# Adafruit_tftcaptouchshield_rev_C.net
KiCad netlist of a schematic drawn in EAGLE
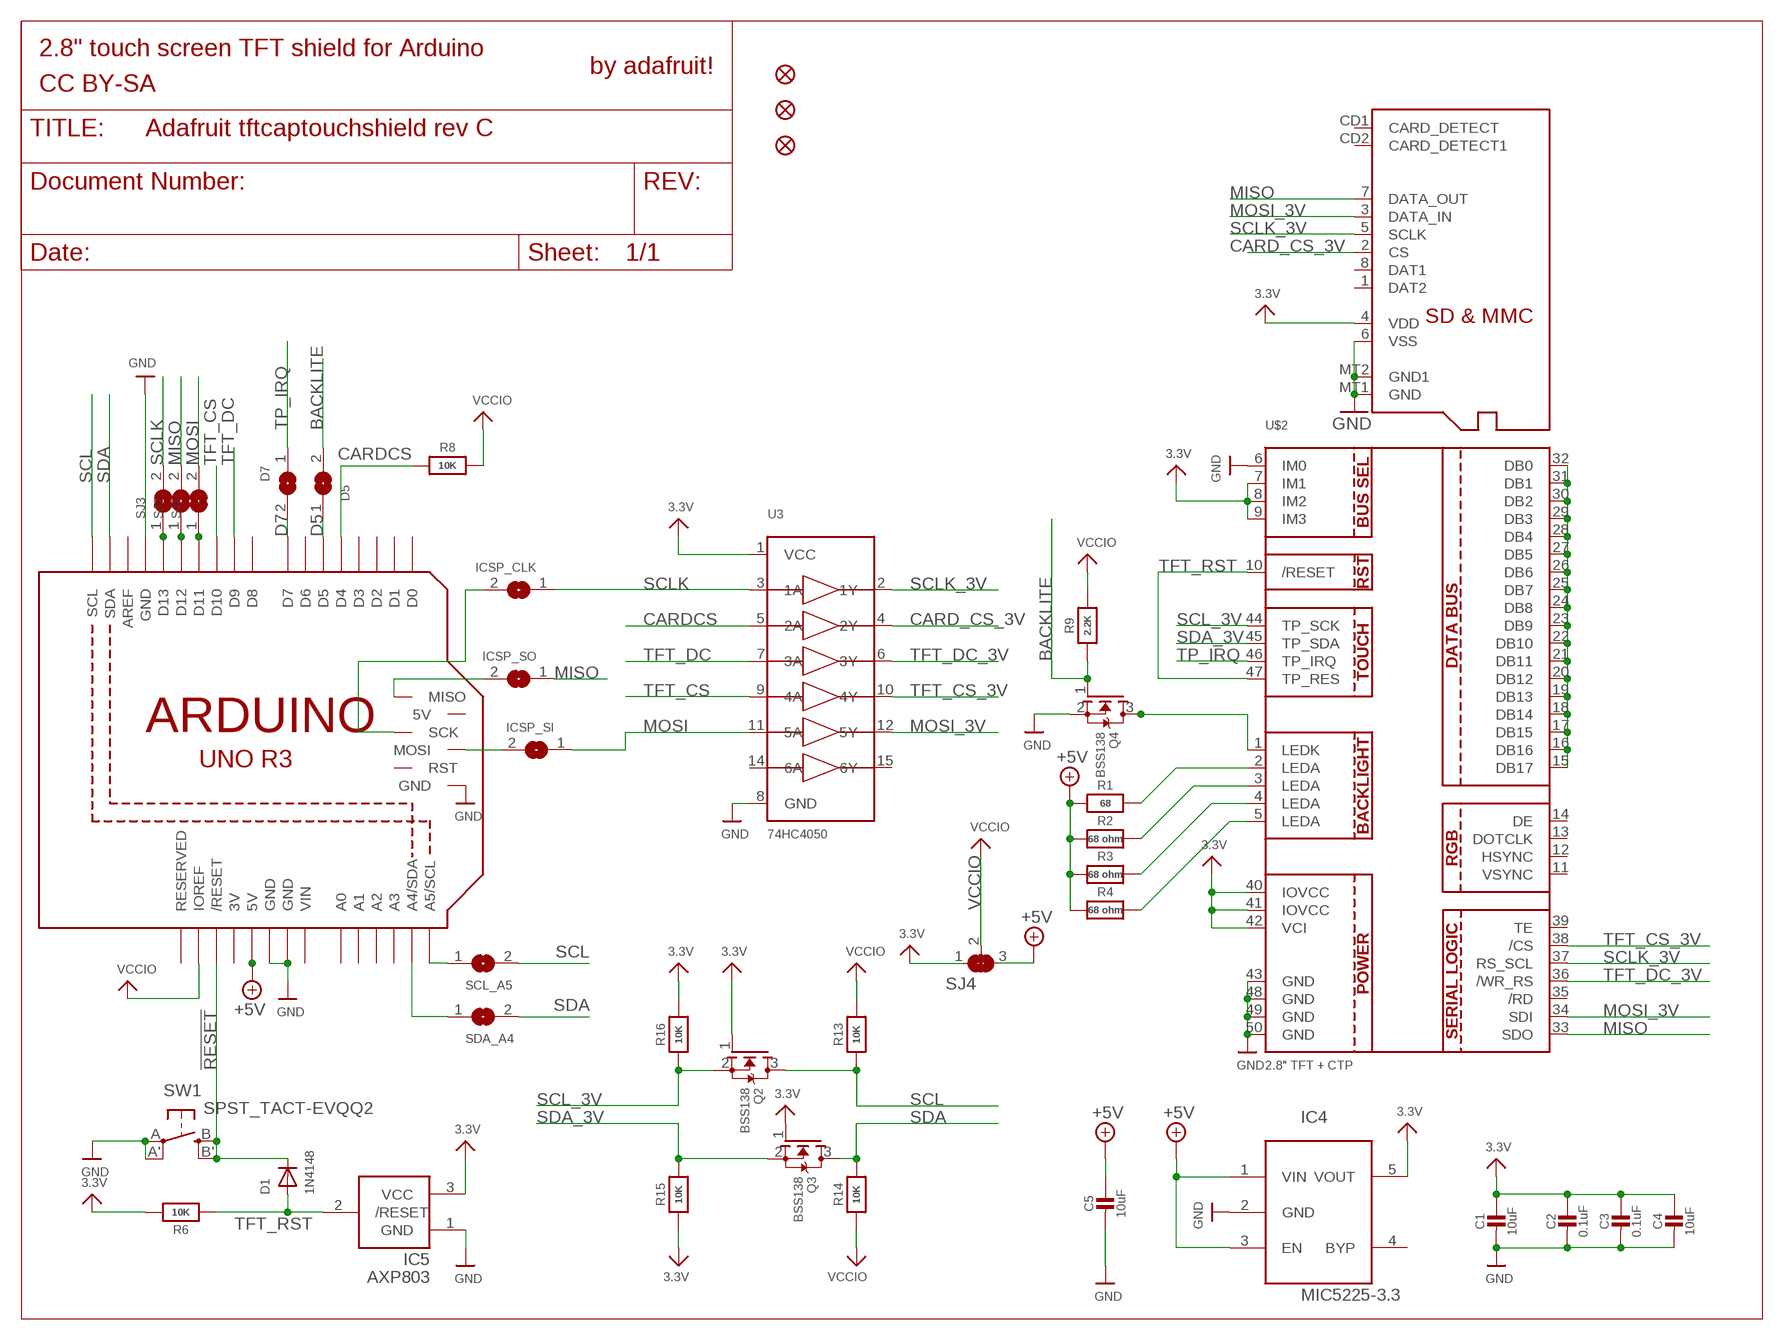
[diagram p0: schematic, sheet 1]

(export (version "E")
  (design (tool "Eeschema 10.0.6"))
  (components
    (comp (ref "C1")
      (value "10uF")
      (footprint "eagle-import:0805-NO")
      (libsource (lib "eagle-import") (part "CAP_CERAMIC0805-NOOUTLINE"))
    )
    (comp (ref "C2")
      (value "0.1uF")
      (footprint "eagle-import:0805-NO")
      (libsource (lib "eagle-import") (part "CAP_CERAMIC0805-NOOUTLINE"))
    )
    (comp (ref "C3")
      (value "0.1uF")
      (footprint "eagle-import:0805-NO")
      (libsource (lib "eagle-import") (part "CAP_CERAMIC0805-NOOUTLINE"))
    )
    (comp (ref "C4")
      (value "10uF")
      (footprint "eagle-import:0805-NO")
      (libsource (lib "eagle-import") (part "CAP_CERAMIC0805-NOOUTLINE"))
    )
    (comp (ref "C5")
      (value "10uF")
      (footprint "eagle-import:0805-NO")
      (libsource (lib "eagle-import") (part "CAP_CERAMIC0805-NOOUTLINE"))
    )
    (comp (ref "D1")
      (value "1N4148")
      (footprint "eagle-import:SOD-323F")
      (libsource (lib "eagle-import") (part "DIODESOD-323F"))
    )
    (comp (ref "D5")
      (value "SOLDERJUMPER")
      (footprint "eagle-import:SOLDERJUMPER_ARROW_NOPASTE")
      (libsource (lib "eagle-import") (part "SOLDERJUMPER"))
    )
    (comp (ref "D7")
      (value "SOLDERJUMPER")
      (footprint "eagle-import:SOLDERJUMPER_ARROW_NOPASTE")
      (libsource (lib "eagle-import") (part "SOLDERJUMPER"))
    )
    (comp (ref "IC4")
      (value "MIC5225-3.3")
      (footprint "eagle-import:SOT23-5L")
      (libsource (lib "eagle-import") (part "LP298XS"))
    )
    (comp (ref "IC5")
      (value "AXP803")
      (footprint "eagle-import:SOT23")
      (libsource (lib "eagle-import") (part "AXP083-SAG"))
    )
    (comp (ref "ICSP_CLK")
      (value "SOLDERJUMPERCLOSED")
      (footprint "eagle-import:SOLDERJUMPER_CLOSEDWIRE")
      (libsource (lib "eagle-import") (part "SOLDERJUMPERCLOSED"))
    )
    (comp (ref "ICSP_SI")
      (value "SOLDERJUMPERCLOSED")
      (footprint "eagle-import:SOLDERJUMPER_CLOSEDWIRE")
      (libsource (lib "eagle-import") (part "SOLDERJUMPERCLOSED"))
    )
    (comp (ref "ICSP_SO")
      (value "SOLDERJUMPERCLOSED")
      (footprint "eagle-import:SOLDERJUMPER_CLOSEDWIRE")
      (libsource (lib "eagle-import") (part "SOLDERJUMPERCLOSED"))
    )
    (comp (ref "Q2")
      (value "BSS138")
      (footprint "eagle-import:SOT23-WIDE")
      (libsource (lib "eagle-import") (part "MOSFET-NWIDE"))
    )
    (comp (ref "Q3")
      (value "BSS138")
      (footprint "eagle-import:SOT23-WIDE")
      (libsource (lib "eagle-import") (part "MOSFET-NWIDE"))
    )
    (comp (ref "Q4")
      (value "BSS138")
      (footprint "eagle-import:SOT23-WIDE")
      (libsource (lib "eagle-import") (part "MOSFET-NWIDE"))
    )
    (comp (ref "R1")
      (value "68")
      (footprint "eagle-import:0805-NO")
      (libsource (lib "eagle-import") (part "RESISTOR0805_NOOUTLINE"))
    )
    (comp (ref "R2")
      (value "68 ohm")
      (footprint "eagle-import:0805-NO")
      (libsource (lib "eagle-import") (part "RESISTOR0805_NOOUTLINE"))
    )
    (comp (ref "R3")
      (value "68 ohm")
      (footprint "eagle-import:0805-NO")
      (libsource (lib "eagle-import") (part "RESISTOR0805_NOOUTLINE"))
    )
    (comp (ref "R4")
      (value "68 ohm")
      (footprint "eagle-import:0805-NO")
      (libsource (lib "eagle-import") (part "RESISTOR0805_NOOUTLINE"))
    )
    (comp (ref "R6")
      (value "10K")
      (footprint "eagle-import:0805-NO")
      (libsource (lib "eagle-import") (part "RESISTOR0805_NOOUTLINE"))
    )
    (comp (ref "R8")
      (value "10K")
      (footprint "eagle-import:0805-NO")
      (libsource (lib "eagle-import") (part "RESISTOR0805_NOOUTLINE"))
    )
    (comp (ref "R9")
      (value "2.2K")
      (footprint "eagle-import:0805-NO")
      (libsource (lib "eagle-import") (part "RESISTOR0805_NOOUTLINE"))
    )
    (comp (ref "R13")
      (value "10K")
      (footprint "eagle-import:0805-NO")
      (libsource (lib "eagle-import") (part "RESISTOR0805_NOOUTLINE"))
    )
    (comp (ref "R14")
      (value "10K")
      (footprint "eagle-import:0805-NO")
      (libsource (lib "eagle-import") (part "RESISTOR0805_NOOUTLINE"))
    )
    (comp (ref "R15")
      (value "10K")
      (footprint "eagle-import:0805-NO")
      (libsource (lib "eagle-import") (part "RESISTOR0805_NOOUTLINE"))
    )
    (comp (ref "R16")
      (value "10K")
      (footprint "eagle-import:0805-NO")
      (libsource (lib "eagle-import") (part "RESISTOR0805_NOOUTLINE"))
    )
    (comp (ref "SCL_A5")
      (value "SOLDERJUMPERREFLOW_NOPASTE")
      (footprint "eagle-import:SOLDERJUMPER_REFLOW_NOPASTE")
      (libsource (lib "eagle-import") (part "SOLDERJUMPERREFLOW_NOPASTE"))
    )
    (comp (ref "SDA_A4")
      (value "SOLDERJUMPERREFLOW_NOPASTE")
      (footprint "eagle-import:SOLDERJUMPER_REFLOW_NOPASTE")
      (libsource (lib "eagle-import") (part "SOLDERJUMPERREFLOW_NOPASTE"))
    )
    (comp (ref "SJ1")
      (value "SOLDERJUMPER")
      (footprint "eagle-import:SOLDERJUMPER_ARROW_NOPASTE")
      (libsource (lib "eagle-import") (part "SOLDERJUMPER"))
    )
    (comp (ref "SJ2")
      (value "SOLDERJUMPER")
      (footprint "eagle-import:SOLDERJUMPER_ARROW_NOPASTE")
      (libsource (lib "eagle-import") (part "SOLDERJUMPER"))
    )
    (comp (ref "SJ3")
      (value "SOLDERJUMPER")
      (footprint "eagle-import:SOLDERJUMPER_ARROW_NOPASTE")
      (libsource (lib "eagle-import") (part "SOLDERJUMPER"))
    )
    (comp (ref "SJ4")
      (value "SOLDERJUMPER_2WAY")
      (footprint "eagle-import:SOLDERJUMPER_2WAY_OPEN_NOPASTE")
      (libsource (lib "eagle-import") (part "SOLDERJUMPER_2WAY"))
    )
    (comp (ref "SW1")
      (value "SPST_TACT-EVQQ2")
      (footprint "eagle-import:EVQ-Q2")
      (libsource (lib "eagle-import") (part "SPST_TACT-EVQQ2"))
    )
    (comp (ref "U$2")
      (value "2.8\" TFT + CTP")
      (footprint "eagle-import:TFT_2.83IN_240X320_50PIN")
      (libsource (lib "eagle-import") (part "DISP_LCD_CTP28_SAMPLE"))
    )
    (comp (ref "U$3")
      (value "MICROSD")
      (footprint "eagle-import:MICROSD")
      (libsource (lib "eagle-import") (part "MICROSD"))
    )
    (comp (ref "U$10")
      (value "FIDUCIAL_1MM")
      (footprint "eagle-import:FIDUCIAL_1MM")
      (libsource (lib "eagle-import") (part "FIDUCIAL_1MM"))
    )
    (comp (ref "U$11")
      (value "FIDUCIAL_1MM")
      (footprint "eagle-import:FIDUCIAL_1MM")
      (libsource (lib "eagle-import") (part "FIDUCIAL_1MM"))
    )
    (comp (ref "U$17")
      (value "ARDUINO_R3_ICSPSMT")
      (footprint "eagle-import:ARDUINOR3_ICSP_SMT")
      (libsource (lib "eagle-import") (part "ARDUINO_R3_ICSPSMT"))
    )
    (comp (ref "U$19")
      (value "FIDUCIAL_1MM")
      (footprint "eagle-import:FIDUCIAL_1MM")
      (libsource (lib "eagle-import") (part "FIDUCIAL_1MM"))
    )
    (comp (ref "U3")
      (value "74HC4050")
      (footprint "eagle-import:SOIC16")
      (libsource (lib "eagle-import") (part "74HC4050D"))
    )
  )
  (nets
    (net (code "1") (name "+5V") (class "Default")
      (node (ref "C5") (pin "1") (pinfunction "1_1") (pintype "passive"))
      (node (ref "IC4") (pin "1") (pinfunction "VIN_1") (pintype "bidirectional"))
      (node (ref "IC4") (pin "3") (pinfunction "EN_3") (pintype "bidirectional"))
      (node (ref "R1") (pin "1") (pinfunction "1_1") (pintype "passive"))
      (node (ref "R2") (pin "1") (pinfunction "1_1") (pintype "passive"))
      (node (ref "R3") (pin "1") (pinfunction "1_1") (pintype "passive"))
      (node (ref "R4") (pin "1") (pinfunction "1_1") (pintype "passive"))
      (node (ref "SJ4") (pin "3") (pinfunction "3_3") (pintype "passive"))
      (node (ref "U$17") (pin "5V") (pinfunction "5V_5V") (pintype "power_in"))
    )
    (net (code "2") (name "/3V") (class "Default")
      (node (ref "U$17") (pin "3V") (pinfunction "3V_3V") (pintype "power_in"))
    )
    (net (code "3") (name "/BACKLITE") (class "Default")
      (node (ref "D5") (pin "2") (pinfunction "2_2") (pintype "passive"))
      (node (ref "Q4") (pin "1") (pinfunction "G_1") (pintype "bidirectional"))
      (node (ref "R9") (pin "1") (pinfunction "1_1") (pintype "passive"))
    )
    (net (code "4") (name "/CARDCS") (class "Default")
      (node (ref "R8") (pin "1") (pinfunction "1_1") (pintype "passive"))
      (node (ref "U$17") (pin "D4") (pinfunction "D4_D4") (pintype "bidirectional"))
      (node (ref "U3") (pin "5") (pinfunction "2A_5") (pintype "bidirectional"))
    )
    (net (code "5") (name "/CARD_CS_3V") (class "Default")
      (node (ref "U$3") (pin "2") (pinfunction "CS_2") (pintype "input"))
      (node (ref "U3") (pin "4") (pinfunction "2Y_4") (pintype "bidirectional"))
    )
    (net (code "6") (name "/D5") (class "Default")
      (node (ref "D5") (pin "1") (pinfunction "1_1") (pintype "passive"))
      (node (ref "U$17") (pin "D5") (pinfunction "D5_D5") (pintype "bidirectional"))
    )
    (net (code "7") (name "/D7") (class "Default")
      (node (ref "D7") (pin "2") (pinfunction "2_2") (pintype "passive"))
      (node (ref "U$17") (pin "D7") (pinfunction "D7_D7") (pintype "bidirectional"))
    )
    (net (code "8") (name "/MISO") (class "Default")
      (node (ref "ICSP_SO") (pin "1") (pinfunction "1_1") (pintype "passive"))
      (node (ref "SJ2") (pin "2") (pinfunction "2_2") (pintype "passive"))
      (node (ref "U$2") (pin "33") (pinfunction "SDO_33") (pintype "bidirectional"))
      (node (ref "U$3") (pin "7") (pinfunction "DATA_OUT_7") (pintype "output"))
    )
    (net (code "9") (name "/MOSI") (class "Default")
      (node (ref "ICSP_SI") (pin "1") (pinfunction "1_1") (pintype "passive"))
      (node (ref "SJ1") (pin "2") (pinfunction "2_2") (pintype "passive"))
      (node (ref "U3") (pin "11") (pinfunction "5A_11") (pintype "bidirectional"))
    )
    (net (code "10") (name "/MOSI_3V") (class "Default")
      (node (ref "U$2") (pin "34") (pinfunction "SDI_34") (pintype "bidirectional"))
      (node (ref "U$3") (pin "3") (pinfunction "DATA_IN_3") (pintype "input"))
      (node (ref "U3") (pin "12") (pinfunction "5Y_12") (pintype "bidirectional"))
    )
    (net (code "11") (name "/SCL") (class "Default")
      (node (ref "Q2") (pin "3") (pinfunction "D_3") (pintype "bidirectional"))
      (node (ref "R13") (pin "1") (pinfunction "1_1") (pintype "passive"))
      (node (ref "SCL_A5") (pin "2") (pinfunction "2_2") (pintype "passive"))
      (node (ref "U$17") (pin "SCL") (pinfunction "SCL_SCL") (pintype "bidirectional"))
    )
    (net (code "12") (name "/SCLK") (class "Default")
      (node (ref "ICSP_CLK") (pin "1") (pinfunction "1_1") (pintype "passive"))
      (node (ref "SJ3") (pin "2") (pinfunction "2_2") (pintype "passive"))
      (node (ref "U3") (pin "3") (pinfunction "1A_3") (pintype "bidirectional"))
    )
    (net (code "13") (name "/SCLK_3V") (class "Default")
      (node (ref "U$2") (pin "37") (pinfunction "RS_SCL_37") (pintype "bidirectional"))
      (node (ref "U$3") (pin "5") (pinfunction "SCLK_5") (pintype "input"))
      (node (ref "U3") (pin "2") (pinfunction "1Y_2") (pintype "bidirectional"))
    )
    (net (code "14") (name "/SCL_3V") (class "Default")
      (node (ref "Q2") (pin "2") (pinfunction "S_2") (pintype "bidirectional"))
      (node (ref "R16") (pin "1") (pinfunction "1_1") (pintype "passive"))
      (node (ref "U$2") (pin "44") (pinfunction "TP_SCK_44") (pintype "bidirectional"))
    )
    (net (code "15") (name "/SDA") (class "Default")
      (node (ref "Q3") (pin "3") (pinfunction "D_3") (pintype "bidirectional"))
      (node (ref "R14") (pin "2") (pinfunction "2_2") (pintype "passive"))
      (node (ref "SDA_A4") (pin "2") (pinfunction "2_2") (pintype "passive"))
      (node (ref "U$17") (pin "SDA") (pinfunction "SDA_SDA") (pintype "bidirectional"))
    )
    (net (code "16") (name "/SDA_3V") (class "Default")
      (node (ref "Q3") (pin "2") (pinfunction "S_2") (pintype "bidirectional"))
      (node (ref "R15") (pin "2") (pinfunction "2_2") (pintype "passive"))
      (node (ref "U$2") (pin "45") (pinfunction "TP_SDA_45") (pintype "bidirectional"))
    )
    (net (code "17") (name "/TFT_CS") (class "Default")
      (node (ref "U$17") (pin "D10") (pinfunction "D10_D10") (pintype "bidirectional"))
      (node (ref "U3") (pin "9") (pinfunction "4A_9") (pintype "bidirectional"))
    )
    (net (code "18") (name "/TFT_CS_3V") (class "Default")
      (node (ref "U$2") (pin "38") (pinfunction "/CS_38") (pintype "bidirectional"))
      (node (ref "U3") (pin "10") (pinfunction "4Y_10") (pintype "bidirectional"))
    )
    (net (code "19") (name "/TFT_DC") (class "Default")
      (node (ref "U$17") (pin "D9") (pinfunction "D9_D9") (pintype "bidirectional"))
      (node (ref "U3") (pin "7") (pinfunction "3A_7") (pintype "bidirectional"))
    )
    (net (code "20") (name "/TFT_DC_3V") (class "Default")
      (node (ref "U$2") (pin "36") (pinfunction "/WR_RS_36") (pintype "bidirectional"))
      (node (ref "U3") (pin "6") (pinfunction "3Y_6") (pintype "bidirectional"))
    )
    (net (code "21") (name "/TFT_RST") (class "Default")
      (node (ref "D1") (pin "A") (pinfunction "A_A") (pintype "passive"))
      (node (ref "IC5") (pin "2") (pinfunction "/RESET_2") (pintype "output"))
      (node (ref "R6") (pin "1") (pinfunction "1_1") (pintype "passive"))
      (node (ref "U$2") (pin "10") (pinfunction "/RESET_10") (pintype "bidirectional"))
      (node (ref "U$2") (pin "47") (pinfunction "TP_RES_47") (pintype "bidirectional"))
    )
    (net (code "22") (name "/TP_IRQ") (class "Default")
      (node (ref "D7") (pin "1") (pinfunction "1_1") (pintype "passive"))
      (node (ref "U$2") (pin "46") (pinfunction "TP_IRQ_46") (pintype "bidirectional"))
    )
    (net (code "23") (name "/VIN") (class "Default")
      (node (ref "U$17") (pin "VIN") (pinfunction "VIN_VIN") (pintype "power_in"))
    )
    (net (code "24") (name "/~{RESET}") (class "Default")
      (node (ref "D1") (pin "C") (pinfunction "C_C") (pintype "passive"))
      (node (ref "SW1") (pin "B") (pinfunction "S_B") (pintype "passive"))
      (node (ref "SW1") (pin "B'") (pinfunction "S1_B'") (pintype "passive"))
      (node (ref "U$17") (pin "RESET") (pinfunction "/RESET_RESET") (pintype "bidirectional"))
    )
    (net (code "25") (name "3.3V") (class "Default")
      (node (ref "C1") (pin "1") (pinfunction "1_1") (pintype "passive"))
      (node (ref "C2") (pin "1") (pinfunction "1_1") (pintype "passive"))
      (node (ref "C3") (pin "1") (pinfunction "1_1") (pintype "passive"))
      (node (ref "C4") (pin "1") (pinfunction "1_1") (pintype "passive"))
      (node (ref "IC4") (pin "5") (pinfunction "VOUT_5") (pintype "bidirectional"))
      (node (ref "IC5") (pin "3") (pinfunction "VCC_3") (pintype "power_in"))
      (node (ref "Q2") (pin "1") (pinfunction "G_1") (pintype "bidirectional"))
      (node (ref "Q3") (pin "1") (pinfunction "G_1") (pintype "bidirectional"))
      (node (ref "R15") (pin "1") (pinfunction "1_1") (pintype "passive"))
      (node (ref "R16") (pin "2") (pinfunction "2_2") (pintype "passive"))
      (node (ref "R6") (pin "2") (pinfunction "2_2") (pintype "passive"))
      (node (ref "SJ4") (pin "1") (pinfunction "1_1") (pintype "passive"))
      (node (ref "U$2") (pin "40") (pinfunction "IOVCC_40") (pintype "bidirectional"))
      (node (ref "U$2") (pin "41") (pinfunction "IOVCC_41") (pintype "bidirectional"))
      (node (ref "U$2") (pin "42") (pinfunction "VCI_42") (pintype "bidirectional"))
      (node (ref "U$2") (pin "7") (pinfunction "IM1_7") (pintype "bidirectional"))
      (node (ref "U$2") (pin "8") (pinfunction "IM2_8") (pintype "bidirectional"))
      (node (ref "U$2") (pin "9") (pinfunction "IM3_9") (pintype "bidirectional"))
      (node (ref "U$3") (pin "4") (pinfunction "VDD_4") (pintype "power_in"))
      (node (ref "U3") (pin "1") (pinfunction "VCC_1") (pintype "bidirectional"))
    )
    (net (code "26") (name "GND") (class "Default")
      (node (ref "C1") (pin "2") (pinfunction "2_2") (pintype "passive"))
      (node (ref "C2") (pin "2") (pinfunction "2_2") (pintype "passive"))
      (node (ref "C3") (pin "2") (pinfunction "2_2") (pintype "passive"))
      (node (ref "C4") (pin "2") (pinfunction "2_2") (pintype "passive"))
      (node (ref "C5") (pin "2") (pinfunction "2_2") (pintype "passive"))
      (node (ref "IC4") (pin "2") (pinfunction "GND_2") (pintype "bidirectional"))
      (node (ref "IC5") (pin "1") (pinfunction "GND_1") (pintype "power_in"))
      (node (ref "Q4") (pin "2") (pinfunction "S_2") (pintype "bidirectional"))
      (node (ref "SW1") (pin "A") (pinfunction "P_A") (pintype "passive"))
      (node (ref "SW1") (pin "A'") (pinfunction "P1_A'") (pintype "passive"))
      (node (ref "U$17") (pin "GND") (pinfunction "GND_GND") (pintype "power_in"))
      (node (ref "U$17") (pin "GND@1") (pinfunction "GND_GND@1") (pintype "power_in"))
      (node (ref "U$17") (pin "GND@2") (pinfunction "GND_GND@2") (pintype "power_in"))
      (node (ref "U$17") (pin "GND@3") (pinfunction "GND_GND@3") (pintype "passive"))
      (node (ref "U$2") (pin "43") (pinfunction "GND_43") (pintype "bidirectional"))
      (node (ref "U$2") (pin "48") (pinfunction "GND_48") (pintype "bidirectional"))
      (node (ref "U$2") (pin "49") (pinfunction "GND_49") (pintype "bidirectional"))
      (node (ref "U$2") (pin "50") (pinfunction "GND_50") (pintype "bidirectional"))
      (node (ref "U$2") (pin "6") (pinfunction "IM0_6") (pintype "bidirectional"))
      (node (ref "U$3") (pin "6") (pinfunction "VSS_6") (pintype "power_in"))
      (node (ref "U$3") (pin "MT1") (pinfunction "GND_MT1") (pintype "power_in"))
      (node (ref "U$3") (pin "MT2") (pinfunction "GND1_MT2") (pintype "power_in"))
      (node (ref "U3") (pin "8") (pinfunction "GND_8") (pintype "bidirectional"))
    )
    (net (code "27") (name "Net-(ICSP_CLK-Pad2)") (class "Default")
      (node (ref "ICSP_CLK") (pin "2") (pinfunction "2_2") (pintype "passive"))
      (node (ref "U$17") (pin "SCK") (pinfunction "SCK_SCK") (pintype "passive"))
    )
    (net (code "28") (name "Net-(ICSP_SI-Pad2)") (class "Default")
      (node (ref "ICSP_SI") (pin "2") (pinfunction "2_2") (pintype "passive"))
      (node (ref "U$17") (pin "MOSI") (pinfunction "MOSI_MOSI") (pintype "passive"))
    )
    (net (code "29") (name "Net-(ICSP_SO-Pad2)") (class "Default")
      (node (ref "ICSP_SO") (pin "2") (pinfunction "2_2") (pintype "passive"))
      (node (ref "U$17") (pin "MISO") (pinfunction "MISO_MISO") (pintype "passive"))
    )
    (net (code "30") (name "Net-(Q4-D)") (class "Default")
      (node (ref "Q4") (pin "3") (pinfunction "D_3") (pintype "bidirectional"))
      (node (ref "U$2") (pin "1") (pinfunction "LEDK_1") (pintype "bidirectional"))
    )
    (net (code "31") (name "Net-(R1-Pad2)") (class "Default")
      (node (ref "R1") (pin "2") (pinfunction "2_2") (pintype "passive"))
      (node (ref "U$2") (pin "2") (pinfunction "LEDA_2") (pintype "bidirectional"))
    )
    (net (code "32") (name "Net-(R2-Pad2)") (class "Default")
      (node (ref "R2") (pin "2") (pinfunction "2_2") (pintype "passive"))
      (node (ref "U$2") (pin "3") (pinfunction "LEDA_3") (pintype "bidirectional"))
    )
    (net (code "33") (name "Net-(R3-Pad2)") (class "Default")
      (node (ref "R3") (pin "2") (pinfunction "2_2") (pintype "passive"))
      (node (ref "U$2") (pin "4") (pinfunction "LEDA_4") (pintype "bidirectional"))
    )
    (net (code "34") (name "Net-(R4-Pad2)") (class "Default")
      (node (ref "R4") (pin "2") (pinfunction "2_2") (pintype "passive"))
      (node (ref "U$2") (pin "5") (pinfunction "LEDA_5") (pintype "bidirectional"))
    )
    (net (code "35") (name "Net-(SJ1-Pad1)") (class "Default")
      (node (ref "SJ1") (pin "1") (pinfunction "1_1") (pintype "passive"))
      (node (ref "U$17") (pin "D11") (pinfunction "D11_D11") (pintype "bidirectional"))
    )
    (net (code "36") (name "Net-(SJ2-Pad1)") (class "Default")
      (node (ref "SJ2") (pin "1") (pinfunction "1_1") (pintype "passive"))
      (node (ref "U$17") (pin "D12") (pinfunction "D12_D12") (pintype "bidirectional"))
    )
    (net (code "37") (name "Net-(SJ3-Pad1)") (class "Default")
      (node (ref "SJ3") (pin "1") (pinfunction "1_1") (pintype "passive"))
      (node (ref "U$17") (pin "D13") (pinfunction "D13_D13") (pintype "bidirectional"))
    )
    (net (code "38") (name "Net-(U$2-DB0)") (class "Default")
      (node (ref "U$2") (pin "15") (pinfunction "DB17_15") (pintype "bidirectional"))
      (node (ref "U$2") (pin "16") (pinfunction "DB16_16") (pintype "bidirectional"))
      (node (ref "U$2") (pin "17") (pinfunction "DB15_17") (pintype "bidirectional"))
      (node (ref "U$2") (pin "18") (pinfunction "DB14_18") (pintype "bidirectional"))
      (node (ref "U$2") (pin "19") (pinfunction "DB13_19") (pintype "bidirectional"))
      (node (ref "U$2") (pin "20") (pinfunction "DB12_20") (pintype "bidirectional"))
      (node (ref "U$2") (pin "21") (pinfunction "DB11_21") (pintype "bidirectional"))
      (node (ref "U$2") (pin "22") (pinfunction "DB10_22") (pintype "bidirectional"))
      (node (ref "U$2") (pin "23") (pinfunction "DB9_23") (pintype "bidirectional"))
      (node (ref "U$2") (pin "24") (pinfunction "DB8_24") (pintype "bidirectional"))
      (node (ref "U$2") (pin "25") (pinfunction "DB7_25") (pintype "bidirectional"))
      (node (ref "U$2") (pin "26") (pinfunction "DB6_26") (pintype "bidirectional"))
      (node (ref "U$2") (pin "27") (pinfunction "DB5_27") (pintype "bidirectional"))
      (node (ref "U$2") (pin "28") (pinfunction "DB4_28") (pintype "bidirectional"))
      (node (ref "U$2") (pin "29") (pinfunction "DB3_29") (pintype "bidirectional"))
      (node (ref "U$2") (pin "30") (pinfunction "DB2_30") (pintype "bidirectional"))
      (node (ref "U$2") (pin "31") (pinfunction "DB1_31") (pintype "bidirectional"))
      (node (ref "U$2") (pin "32") (pinfunction "DB0_32") (pintype "bidirectional"))
    )
    (net (code "39") (name "Net-(U$17-A4{slash}SDA)") (class "Default")
      (node (ref "SDA_A4") (pin "1") (pinfunction "1_1") (pintype "passive"))
      (node (ref "U$17") (pin "A4") (pinfunction "A4/SDA_A4") (pintype "bidirectional"))
    )
    (net (code "40") (name "Net-(U$17-A5{slash}SCL)") (class "Default")
      (node (ref "SCL_A5") (pin "1") (pinfunction "1_1") (pintype "passive"))
      (node (ref "U$17") (pin "A5") (pinfunction "A5/SCL_A5") (pintype "bidirectional"))
    )
    (net (code "41") (name "VCCIO") (class "Default")
      (node (ref "R13") (pin "2") (pinfunction "2_2") (pintype "passive"))
      (node (ref "R14") (pin "1") (pinfunction "1_1") (pintype "passive"))
      (node (ref "R8") (pin "2") (pinfunction "2_2") (pintype "passive"))
      (node (ref "R9") (pin "2") (pinfunction "2_2") (pintype "passive"))
      (node (ref "SJ4") (pin "2") (pinfunction "2_2") (pintype "passive"))
      (node (ref "U$17") (pin "IOREF") (pinfunction "IOREF_IOREF") (pintype "output"))
    )
    (net (code "42") (name "unconnected-(IC4-BYP-Pad4)") (class "Default")
      (node (ref "IC4") (pin "4") (pinfunction "BYP_4") (pintype "bidirectional"))
    )
    (net (code "43") (name "unconnected-(U$2-DE-Pad14)") (class "Default")
      (node (ref "U$2") (pin "14") (pinfunction "DE_14") (pintype "bidirectional"))
    )
    (net (code "44") (name "unconnected-(U$2-DOTCLK-Pad13)") (class "Default")
      (node (ref "U$2") (pin "13") (pinfunction "DOTCLK_13") (pintype "bidirectional"))
    )
    (net (code "45") (name "unconnected-(U$2-HSYNC-Pad12)") (class "Default")
      (node (ref "U$2") (pin "12") (pinfunction "HSYNC_12") (pintype "bidirectional"))
    )
    (net (code "46") (name "unconnected-(U$2-TE-Pad39)") (class "Default")
      (node (ref "U$2") (pin "39") (pinfunction "TE_39") (pintype "bidirectional"))
    )
    (net (code "47") (name "unconnected-(U$2-VSYNC-Pad11)") (class "Default")
      (node (ref "U$2") (pin "11") (pinfunction "VSYNC_11") (pintype "bidirectional"))
    )
    (net (code "48") (name "unconnected-(U$2-{slash}RD-Pad35)") (class "Default")
      (node (ref "U$2") (pin "35") (pinfunction "/RD_35") (pintype "bidirectional"))
    )
    (net (code "49") (name "unconnected-(U$3-CARD_DETECT-PadCD1)") (class "Default")
      (node (ref "U$3") (pin "CD1") (pinfunction "CARD_DETECT_CD1") (pintype "passive"))
    )
    (net (code "50") (name "unconnected-(U$3-CARD_DETECT1-PadCD2)") (class "Default")
      (node (ref "U$3") (pin "CD2") (pinfunction "CARD_DETECT1_CD2") (pintype "passive"))
    )
    (net (code "51") (name "unconnected-(U$3-DAT1-Pad8)") (class "Default")
      (node (ref "U$3") (pin "8") (pinfunction "DAT1_8") (pintype "bidirectional"))
    )
    (net (code "52") (name "unconnected-(U$3-DAT2-Pad1)") (class "Default")
      (node (ref "U$3") (pin "1") (pinfunction "DAT2_1") (pintype "bidirectional"))
    )
    (net (code "53") (name "unconnected-(U$17-5V-Pad5V_ICSP)") (class "Default")
      (node (ref "U$17") (pin "5V_ICSP") (pinfunction "5V_5V_ICSP") (pintype "passive"))
    )
    (net (code "54") (name "unconnected-(U$17-PadA0)") (class "Default")
      (node (ref "U$17") (pin "A0") (pinfunction "A0_A0") (pintype "bidirectional"))
    )
    (net (code "55") (name "unconnected-(U$17-PadA1)") (class "Default")
      (node (ref "U$17") (pin "A1") (pinfunction "A1_A1") (pintype "bidirectional"))
    )
    (net (code "56") (name "unconnected-(U$17-PadA2)") (class "Default")
      (node (ref "U$17") (pin "A2") (pinfunction "A2_A2") (pintype "bidirectional"))
    )
    (net (code "57") (name "unconnected-(U$17-PadA3)") (class "Default")
      (node (ref "U$17") (pin "A3") (pinfunction "A3_A3") (pintype "bidirectional"))
    )
    (net (code "58") (name "unconnected-(U$17-PadAREF)") (class "Default")
      (node (ref "U$17") (pin "AREF") (pinfunction "AREF_AREF") (pintype "bidirectional"))
    )
    (net (code "59") (name "unconnected-(U$17-PadD0)") (class "Default")
      (node (ref "U$17") (pin "D0") (pinfunction "D0_D0") (pintype "bidirectional"))
    )
    (net (code "60") (name "unconnected-(U$17-PadD1)") (class "Default")
      (node (ref "U$17") (pin "D1") (pinfunction "D1_D1") (pintype "bidirectional"))
    )
    (net (code "61") (name "unconnected-(U$17-PadD2)") (class "Default")
      (node (ref "U$17") (pin "D2") (pinfunction "D2_D2") (pintype "bidirectional"))
    )
    (net (code "62") (name "unconnected-(U$17-PadD3)") (class "Default")
      (node (ref "U$17") (pin "D3") (pinfunction "D3_D3") (pintype "bidirectional"))
    )
    (net (code "63") (name "unconnected-(U$17-PadD6)") (class "Default")
      (node (ref "U$17") (pin "D6") (pinfunction "D6_D6") (pintype "bidirectional"))
    )
    (net (code "64") (name "unconnected-(U$17-PadD8)") (class "Default")
      (node (ref "U$17") (pin "D8") (pinfunction "D8_D8") (pintype "bidirectional"))
    )
    (net (code "65") (name "unconnected-(U$17-PadRESERVED)") (class "Default")
      (node (ref "U$17") (pin "RESERVED") (pinfunction "RESERVED_RESERVED") (pintype "no_connect"))
    )
    (net (code "66") (name "unconnected-(U$17-RST-PadRESET_ICSP)") (class "Default")
      (node (ref "U$17") (pin "RESET_ICSP") (pinfunction "RST_RESET_ICSP") (pintype "passive"))
    )
    (net (code "67") (name "unconnected-(U3-6A-Pad14)") (class "Default")
      (node (ref "U3") (pin "14") (pinfunction "6A_14") (pintype "bidirectional"))
    )
    (net (code "68") (name "unconnected-(U3-6Y-Pad15)") (class "Default")
      (node (ref "U3") (pin "15") (pinfunction "6Y_15") (pintype "bidirectional"))
    )
  )
)
